# ASwitch.net
KiCad netlist of a schematic drawn in Altium Designer
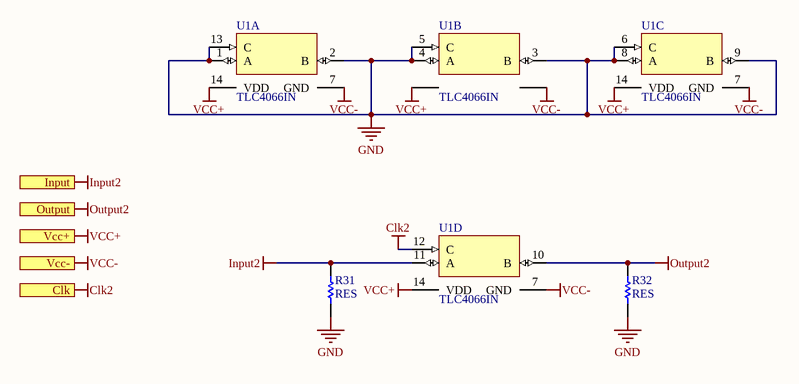
[diagram p0: ASwitch.SchDoc]

(export (version "E")
  (design (tool "Eeschema 10.0.6"))
  (components
    (comp (ref "R31") (value "RES") (footprint "0805") (libsource (lib "LIBEBAL") (part "RES")))
    (comp (ref "R32") (value "RES") (footprint "0805") (libsource (lib "LIBEBAL") (part "RES")))
    (comp (ref "U1")
      (value "TLC4066IN")
      (footprint "N014")
      (description "Quadruple Bilateral Analog Switch")
      (fields (field (name "PUBLISHER") "Altium Limited"))
      (libsource (lib "TI Logic Switch") (part "TLC4066IN"))
    )
  )
  (nets
    (net (code "1") (name "Clk2") (class "Default")
      (node (ref "U1") (pin "12") (pinfunction "C_12") (pintype "input"))
    )
    (net (code "2") (name "GND") (class "Default")
      (node (ref "R31") (pin "1") (pinfunction "1_1") (pintype "passive"))
      (node (ref "R32") (pin "1") (pinfunction "1_1") (pintype "passive"))
      (node (ref "U1") (pin "1") (pinfunction "A_1") (pintype "bidirectional"))
      (node (ref "U1") (pin "13") (pinfunction "C_13") (pintype "input"))
      (node (ref "U1") (pin "2") (pinfunction "B_2") (pintype "bidirectional"))
      (node (ref "U1") (pin "3") (pinfunction "B_3") (pintype "bidirectional"))
      (node (ref "U1") (pin "4") (pinfunction "A_4") (pintype "bidirectional"))
      (node (ref "U1") (pin "5") (pinfunction "C_5") (pintype "input"))
      (node (ref "U1") (pin "6") (pinfunction "C_6") (pintype "input"))
      (node (ref "U1") (pin "7") (pinfunction "GND_7") (pintype "power_in"))
      (node (ref "U1") (pin "8") (pinfunction "A_8") (pintype "bidirectional"))
      (node (ref "U1") (pin "9") (pinfunction "B_9") (pintype "bidirectional"))
    )
    (net (code "3") (name "Input2") (class "Default")
      (node (ref "R31") (pin "2") (pinfunction "2_2") (pintype "passive"))
      (node (ref "U1") (pin "11") (pinfunction "A_11") (pintype "bidirectional"))
    )
    (net (code "4") (name "Output2") (class "Default")
      (node (ref "R32") (pin "2") (pinfunction "2_2") (pintype "passive"))
      (node (ref "U1") (pin "10") (pinfunction "B_10") (pintype "bidirectional"))
    )
    (net (code "5") (name "VCC+") (class "Default")
      (node (ref "U1") (pin "14") (pinfunction "VDD_14") (pintype "power_in"))
    )
  )
)
